# keymanager-1_0.net
KiCad netlist of a schematic drawn in EAGLE
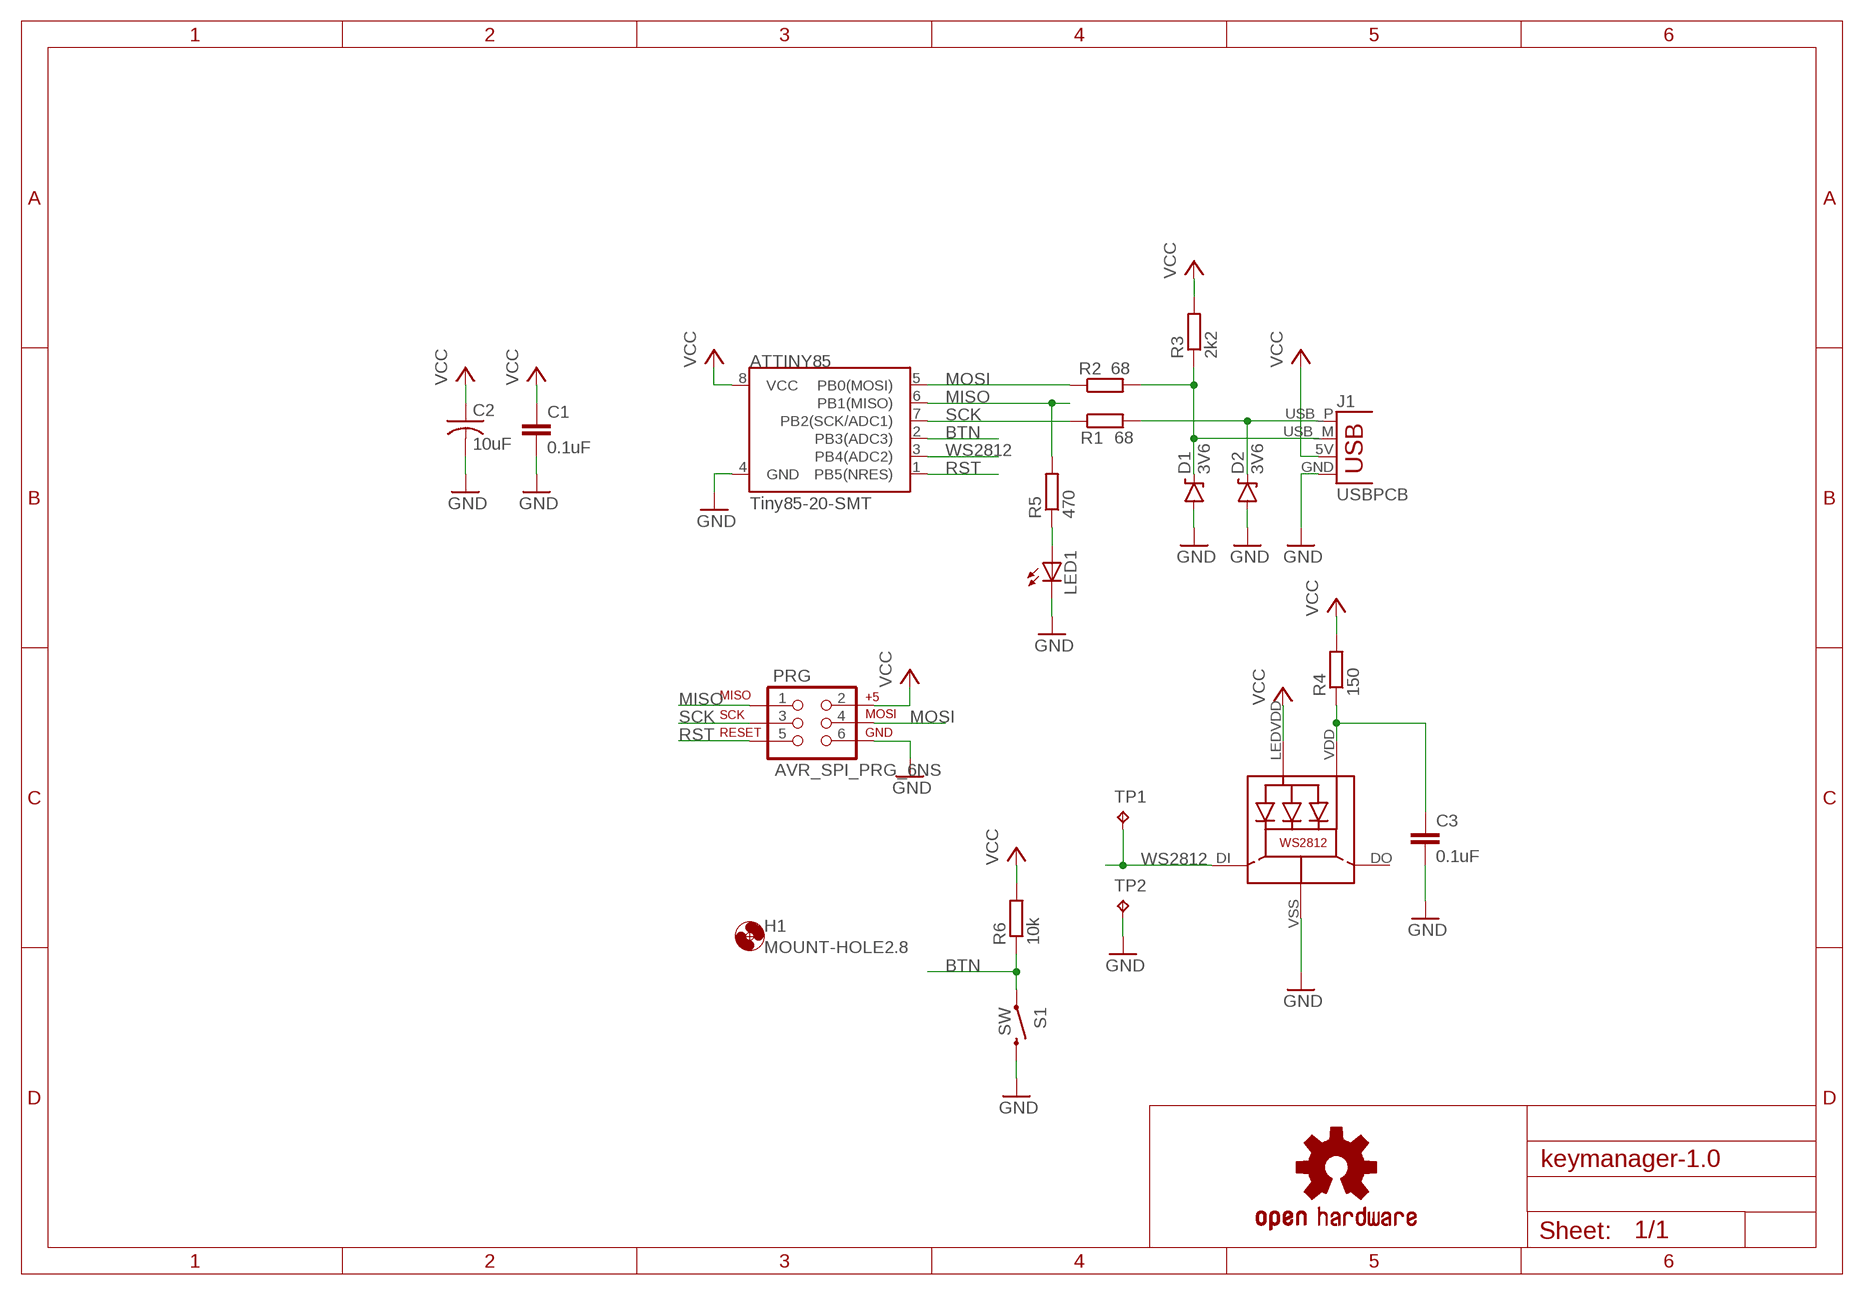
[diagram p0: schematic, sheet 1]

(export (version "E")
  (design (tool "Eeschema 10.0.6"))
  (components
    (comp (ref "ATTINY85")
      (value "Tiny85-20-SMT")
      (footprint "eagle-import:SO08-EIAJ")
      (libsource (lib "eagle-import") (part "ATTINY45TINY85-20-SMT"))
    )
    (comp (ref "C1")
      (value "0.1uF")
      (footprint "eagle-import:C1206")
      (libsource (lib "eagle-import") (part "C-EUC1206"))
    )
    (comp (ref "C2")
      (value "10uF")
      (footprint "eagle-import:C1206")
      (libsource (lib "eagle-import") (part "C-USC1206"))
    )
    (comp (ref "C3")
      (value "0.1uF")
      (footprint "eagle-import:C1206")
      (libsource (lib "eagle-import") (part "C-EUC1206"))
    )
    (comp (ref "D1")
      (value "3V6")
      (footprint "eagle-import:SOD-323")
      (libsource (lib "eagle-import") (part "DIODE-ZENER3.3V"))
    )
    (comp (ref "D2")
      (value "3V6")
      (footprint "eagle-import:SOD-323")
      (libsource (lib "eagle-import") (part "DIODE-ZENER3.3V"))
    )
    (comp (ref "H1")
      (value "MOUNT-HOLE2.8")
      (footprint "eagle-import:2,8")
      (libsource (lib "eagle-import") (part "MOUNT-HOLE2.8"))
    )
    (comp (ref "J1")
      (value "USBPCB")
      (footprint "eagle-import:USB-A-PCB")
      (libsource (lib "eagle-import") (part "USBPCB"))
    )
    (comp (ref "LED1")
      (value "LEDSMT1206")
      (footprint "eagle-import:1206")
      (libsource (lib "eagle-import") (part "LEDSMT1206"))
    )
    (comp (ref "LOGO1")
      (value "OSHW-LOGOS")
      (footprint "eagle-import:OSHW-LOGO-S")
      (libsource (lib "eagle-import") (part "OSHW-LOGOS"))
    )
    (comp (ref "PRG")
      (value "AVR_SPI_PRG_6NS")
      (footprint "eagle-import:2X3-NS")
      (libsource (lib "eagle-import") (part "AVR_SPI_PRG_6NS"))
    )
    (comp (ref "R1")
      (value "68")
      (footprint "eagle-import:R1206")
      (libsource (lib "eagle-import") (part "R-EU_R1206"))
    )
    (comp (ref "R2")
      (value "68")
      (footprint "eagle-import:R1206")
      (libsource (lib "eagle-import") (part "R-EU_R1206"))
    )
    (comp (ref "R3")
      (value "2k2")
      (footprint "eagle-import:R1206")
      (libsource (lib "eagle-import") (part "R-EU_R1206"))
    )
    (comp (ref "R4")
      (value "150")
      (footprint "eagle-import:R1206")
      (libsource (lib "eagle-import") (part "R-EU_R1206"))
    )
    (comp (ref "R5")
      (value "470")
      (footprint "eagle-import:R1206")
      (libsource (lib "eagle-import") (part "R-EU_R1206"))
    )
    (comp (ref "R6")
      (value "10k")
      (footprint "eagle-import:R1206")
      (libsource (lib "eagle-import") (part "R-EU_R1206"))
    )
    (comp (ref "S1")
      (value "SW")
      (footprint "eagle-import:TACTILE-SWITCH-SMD")
      (libsource (lib "eagle-import") (part "SWITCH-MOMENTARY-2SMD"))
    )
    (comp (ref "TP1")
      (value "TPB1,27")
      (footprint "eagle-import:B1,27")
      (libsource (lib "eagle-import") (part "TPB1,27"))
    )
    (comp (ref "TP2")
      (value "TPB1,27")
      (footprint "eagle-import:B1,27")
      (libsource (lib "eagle-import") (part "TPB1,27"))
    )
    (comp (ref "WS2812")
      (value "WS2812")
      (footprint "eagle-import:WS2812")
      (libsource (lib "eagle-import") (part "WS2812"))
    )
  )
  (nets
    (net (code "1") (name "/BTN") (class "Default")
      (node (ref "ATTINY85") (pin "2") (pinfunction "PB3(ADC3)_2") (pintype "bidirectional"))
      (node (ref "R6") (pin "1") (pinfunction "1_1") (pintype "passive"))
      (node (ref "S1") (pin "1") (pinfunction "1_1") (pintype "passive"))
    )
    (net (code "2") (name "/MISO") (class "Default")
      (node (ref "ATTINY85") (pin "6") (pinfunction "PB1(MISO)_6") (pintype "bidirectional"))
      (node (ref "PRG") (pin "1") (pinfunction "1_1") (pintype "passive"))
      (node (ref "R5") (pin "2") (pinfunction "2_2") (pintype "passive"))
    )
    (net (code "3") (name "/MOSI") (class "Default")
      (node (ref "ATTINY85") (pin "5") (pinfunction "PB0(MOSI)_5") (pintype "bidirectional"))
      (node (ref "PRG") (pin "4") (pinfunction "4_4") (pintype "passive"))
      (node (ref "R2") (pin "1") (pinfunction "1_1") (pintype "passive"))
    )
    (net (code "4") (name "/RST") (class "Default")
      (node (ref "ATTINY85") (pin "1") (pinfunction "PB5(NRES)_1") (pintype "bidirectional"))
      (node (ref "PRG") (pin "5") (pinfunction "5_5") (pintype "passive"))
    )
    (net (code "5") (name "/SCK") (class "Default")
      (node (ref "ATTINY85") (pin "7") (pinfunction "PB2(SCK/ADC1)_7") (pintype "bidirectional"))
      (node (ref "PRG") (pin "3") (pinfunction "3_3") (pintype "passive"))
      (node (ref "R1") (pin "1") (pinfunction "1_1") (pintype "passive"))
    )
    (net (code "6") (name "/WS2812") (class "Default")
      (node (ref "ATTINY85") (pin "3") (pinfunction "PB4(ADC2)_3") (pintype "bidirectional"))
      (node (ref "TP1") (pin "TP") (pinfunction "TP_TP") (pintype "input"))
      (node (ref "WS2812") (pin "DI") (pinfunction "DI_DI") (pintype "input"))
    )
    (net (code "7") (name "GND") (class "Default")
      (node (ref "ATTINY85") (pin "4") (pinfunction "GND_4") (pintype "bidirectional"))
      (node (ref "C1") (pin "2") (pinfunction "2_2") (pintype "passive"))
      (node (ref "C2") (pin "2") (pinfunction "2_2") (pintype "passive"))
      (node (ref "C3") (pin "2") (pinfunction "2_2") (pintype "passive"))
      (node (ref "D1") (pin "A") (pinfunction "A_A") (pintype "passive"))
      (node (ref "D2") (pin "A") (pinfunction "A_A") (pintype "passive"))
      (node (ref "J1") (pin "GND") (pinfunction "GND_GND") (pintype "bidirectional"))
      (node (ref "LED1") (pin "C") (pinfunction "C_C") (pintype "passive"))
      (node (ref "PRG") (pin "6") (pinfunction "6_6") (pintype "passive"))
      (node (ref "S1") (pin "3") (pinfunction "2_3") (pintype "passive"))
      (node (ref "TP2") (pin "TP") (pinfunction "TP_TP") (pintype "input"))
      (node (ref "WS2812") (pin "VSS") (pinfunction "GND_VSS") (pintype "power_in"))
    )
    (net (code "8") (name "Net-(C3-Pad1)") (class "Default")
      (node (ref "C3") (pin "1") (pinfunction "1_1") (pintype "passive"))
      (node (ref "R4") (pin "1") (pinfunction "1_1") (pintype "passive"))
      (node (ref "WS2812") (pin "VDD") (pinfunction "VDD_VDD") (pintype "power_in"))
    )
    (net (code "9") (name "Net-(J1-D+)") (class "Default")
      (node (ref "D2") (pin "C") (pinfunction "C_C") (pintype "passive"))
      (node (ref "J1") (pin "USB_P") (pinfunction "D+_USB_P") (pintype "bidirectional"))
      (node (ref "R1") (pin "2") (pinfunction "2_2") (pintype "passive"))
    )
    (net (code "10") (name "Net-(J1-D-)") (class "Default")
      (node (ref "D1") (pin "C") (pinfunction "C_C") (pintype "passive"))
      (node (ref "J1") (pin "USB_M") (pinfunction "D-_USB_M") (pintype "bidirectional"))
      (node (ref "R2") (pin "2") (pinfunction "2_2") (pintype "passive"))
      (node (ref "R3") (pin "1") (pinfunction "1_1") (pintype "passive"))
    )
    (net (code "11") (name "Net-(LED1-PadA)") (class "Default")
      (node (ref "LED1") (pin "A") (pinfunction "A_A") (pintype "passive"))
      (node (ref "R5") (pin "1") (pinfunction "1_1") (pintype "passive"))
    )
    (net (code "12") (name "VCC") (class "Default")
      (node (ref "ATTINY85") (pin "8") (pinfunction "VCC_8") (pintype "bidirectional"))
      (node (ref "C1") (pin "1") (pinfunction "1_1") (pintype "passive"))
      (node (ref "C2") (pin "1") (pinfunction "1_1") (pintype "passive"))
      (node (ref "J1") (pin "5V") (pinfunction "VBUS_5V") (pintype "bidirectional"))
      (node (ref "PRG") (pin "2") (pinfunction "2_2") (pintype "passive"))
      (node (ref "R3") (pin "2") (pinfunction "2_2") (pintype "passive"))
      (node (ref "R4") (pin "2") (pinfunction "2_2") (pintype "passive"))
      (node (ref "R6") (pin "2") (pinfunction "2_2") (pintype "passive"))
      (node (ref "WS2812") (pin "LEDVDD") (pinfunction "LEDVDD_LEDVDD") (pintype "power_in"))
    )
    (net (code "13") (name "unconnected-(WS2812-PadDO)") (class "Default")
      (node (ref "WS2812") (pin "DO") (pinfunction "DO_DO") (pintype "output"))
    )
  )
)
